# Pressure_module.net
KiCad netlist of a schematic drawn in EAGLE
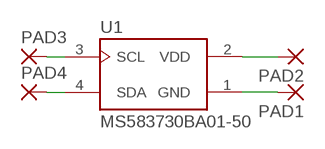
[diagram p0: schematic, sheet 1]

(export (version "E")
  (design (tool "Eeschema 10.0.6"))
  (components
    (comp (ref "PAD1")
      (value "1,6/0,8")
      (footprint "eagle-import:1,6_0,8")
      (libsource (lib "eagle-import") (part "1,6/0,8"))
    )
    (comp (ref "PAD2")
      (value "1,6/0,8")
      (footprint "eagle-import:1,6_0,8")
      (libsource (lib "eagle-import") (part "1,6/0,8"))
    )
    (comp (ref "PAD3")
      (value "1,6/0,8")
      (footprint "eagle-import:1,6_0,8")
      (libsource (lib "eagle-import") (part "1,6/0,8"))
    )
    (comp (ref "PAD4")
      (value "1,6/0,8")
      (footprint "eagle-import:1,6_0,8")
      (libsource (lib "eagle-import") (part "1,6/0,8"))
    )
    (comp (ref "U1")
      (value "MS583730BA01-50")
      (footprint "eagle-import:TE_MS583730BA01-50")
      (fields (field (name "DIGI-KEY_PART_NUMBER") "223-1704-1-ND") (field (name "MF") "TE Connectivity"))
      (libsource (lib "eagle-import") (part "MS583730BA01-50"))
    )
  )
  (nets
    (net (code "1") (name "Net-(PAD1-P)") (class "Default")
      (node (ref "PAD1") (pin "1") (pinfunction "P_1") (pintype "passive"))
      (node (ref "U1") (pin "1") (pinfunction "GND_1") (pintype "power_in"))
    )
    (net (code "2") (name "Net-(PAD2-P)") (class "Default")
      (node (ref "PAD2") (pin "1") (pinfunction "P_1") (pintype "passive"))
      (node (ref "U1") (pin "2") (pinfunction "VDD_2") (pintype "power_in"))
    )
    (net (code "3") (name "Net-(PAD3-P)") (class "Default")
      (node (ref "PAD3") (pin "1") (pinfunction "P_1") (pintype "passive"))
      (node (ref "U1") (pin "3") (pinfunction "SCL_3") (pintype "input"))
    )
    (net (code "4") (name "Net-(PAD4-P)") (class "Default")
      (node (ref "PAD4") (pin "1") (pinfunction "P_1") (pintype "passive"))
      (node (ref "U1") (pin "4") (pinfunction "SDA_4") (pintype "bidirectional"))
    )
  )
)
